# 12V_Supply.net
KiCad netlist of a schematic drawn in Altium Designer
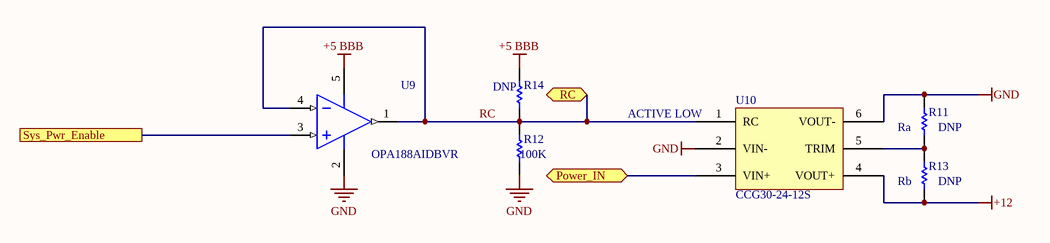
[diagram p0: 12V_Supply.SchDoc]

(export (version "E")
  (design (tool "Eeschema 10.0.6"))
  (components
    (comp (ref "R11")
      (value "DNP")
      (footprint "RESC0805(2012)_M")
      (description "Vout = 12.05 ­ (445.7 / 63.1+Ra)")
      (libsource (lib "Altium Content Vault") (part "CMP-1013-00017-1"))
    )
    (comp (ref "R12")
      (value "RES SMD 100K OHM 1% 1/8W 0805")
      (footprint "RESC0805(2012)_M")
      (fields
        (field (name "MANUFACTURER") "Vishay")
        (field (name "MANUFACTURER PART NUMBER") "CRCW0805100KFKEA")
        (field (name "TOLERANCE") "1%")
        (field (name "RESISTANCE") "100K")
      )
      (libsource (lib "Altium Content Vault") (part "CMP-1013-00017-1"))
    )
    (comp (ref "R13")
      (value "DNP")
      (footprint "RESC0805(2012)_M")
      (description "Vout = 12.05 + (50.96 / 22+Rb)")
      (libsource (lib "Altium Content Vault") (part "CMP-1013-00017-1"))
    )
    (comp (ref "R14")
      (value "DNP")
      (footprint "RESC0805(2012)_M")
      (description "RES SMD 100K OHM 1% 1/8W 0805")
      (fields
        (field (name "MANUFACTURER") "Vishay")
        (field (name "MANUFACTURER PART NUMBER") "CRCW0805100KFKEA")
      )
      (libsource (lib "Altium Content Vault") (part "CMP-1013-00017-1"))
    )
    (comp (ref "U9")
      (value "OPA188AIDBVR")
      (footprint "DBV0005A_L")
      (fields (field (name "MANUFACTURER") "Texas Instruments"))
      (libsource (lib "Altium Content Vault") (part "CMP-0809-00006-2"))
    )
    (comp (ref "U10")
      (value "CCG30-24-12S")
      (footprint "PXB15-24WD05/N")
      (description "DC DC CONVERTER 12V 30W")
      (fields
        (field (name "MANUFACTURER") "TDK-Lambda Americas Inc.")
        (field (name "MANUFACTURER PART NUMBER") "CCG302412S")
      )
      (libsource (lib "ZLS_Schematic_lib") (part "CCG302412S"))
    )
  )
  (nets
    (net (code "1") (name "+5 BBB") (class "Default")
      (node (ref "R14") (pin "1") (pinfunction "1_1") (pintype "passive"))
      (node (ref "U9") (pin "5") (pinfunction "V+_5") (pintype "power_in"))
    )
    (net (code "2") (name "+12") (class "Default")
      (node (ref "R13") (pin "1") (pinfunction "1_1") (pintype "passive"))
      (node (ref "U10") (pin "4") (pinfunction "VOUT+_4") (pintype "passive"))
    )
    (net (code "3") (name "/Power_IN") (class "Default")
      (node (ref "U10") (pin "3") (pinfunction "VIN+_3") (pintype "passive"))
    )
    (net (code "4") (name "/RC") (class "Default")
      (node (ref "R12") (pin "1") (pinfunction "1_1") (pintype "passive"))
      (node (ref "R14") (pin "2") (pinfunction "2_2") (pintype "passive"))
      (node (ref "U10") (pin "1") (pinfunction "RC_1") (pintype "passive"))
      (node (ref "U9") (pin "1") (pinfunction "OUT_1") (pintype "output"))
      (node (ref "U9") (pin "4") (pinfunction "IN-_4") (pintype "input"))
    )
    (net (code "5") (name "/Sys_Pwr_Enable") (class "Default")
      (node (ref "U9") (pin "3") (pinfunction "IN+_3") (pintype "input"))
    )
    (net (code "6") (name "GND") (class "Default")
      (node (ref "R11") (pin "2") (pinfunction "2_2") (pintype "passive"))
      (node (ref "R12") (pin "2") (pinfunction "2_2") (pintype "passive"))
      (node (ref "U10") (pin "2") (pinfunction "VIN-_2") (pintype "passive"))
      (node (ref "U10") (pin "6") (pinfunction "VOUT-_6") (pintype "passive"))
      (node (ref "U9") (pin "2") (pinfunction "V-_2") (pintype "power_in"))
    )
    (net (code "7") (name "Net-(U10-TRIM)") (class "Default")
      (node (ref "R11") (pin "1") (pinfunction "1_1") (pintype "passive"))
      (node (ref "R13") (pin "2") (pinfunction "2_2") (pintype "passive"))
      (node (ref "U10") (pin "5") (pinfunction "TRIM_5") (pintype "passive"))
    )
  )
)
